# Simple-BUG-BC557.net
KiCad netlist of a schematic drawn in EAGLE
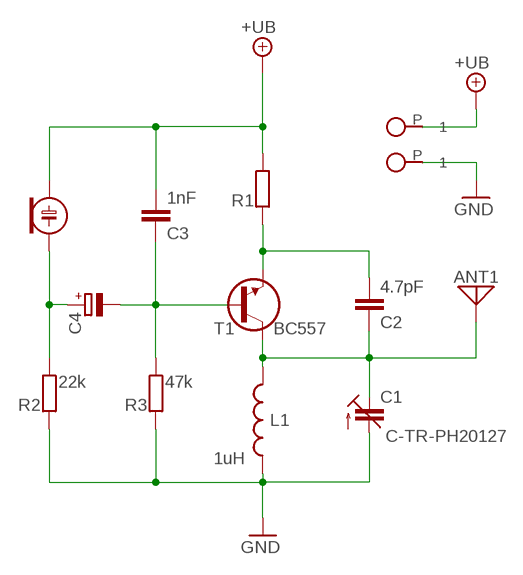
[diagram p0: schematic, sheet 1]

(export (version "E")
  (design (tool "Eeschema 10.0.6"))
  (components
    (comp (ref "+")
      (value "SPAD")
      (footprint "eagle-import:SPAD")
      (libsource (lib "eagle-import") (part "SPAD"))
    )
    (comp (ref "ANT1")
      (value "ANT")
      (footprint "eagle-import:SPAD")
      (libsource (lib "eagle-import") (part "ANT"))
    )
    (comp (ref "C1")
      (value "C-TR-PH20127")
      (footprint "eagle-import:TRIM808-45")
      (libsource (lib "eagle-import") (part "C-TR-PH20127-45-2P23"))
    )
    (comp (ref "C2")
      (value "4.7pF")
      (footprint "eagle-import:C050-020X036")
      (libsource (lib "eagle-import") (part "C050-020X036"))
    )
    (comp (ref "C3")
      (value "1nF")
      (footprint "eagle-import:C050-020X036")
      (libsource (lib "eagle-import") (part "C050-020X036"))
    )
    (comp (ref "C4")
      (value "CPOLE2,5-3")
      (footprint "eagle-import:E2,5-3")
      (libsource (lib "eagle-import") (part "CPOLE2,5-3"))
    )
    (comp (ref "ECM")
      (value "ECM-5")
      (footprint "eagle-import:ECM-5")
      (libsource (lib "eagle-import") (part "ECM-5"))
    )
    (comp (ref "L1")
      (value "1uH")
      (footprint "eagle-import:L-04_7")
      (libsource (lib "eagle-import") (part "L04/7"))
    )
    (comp (ref "R1")
      (value "R0202V")
      (footprint "eagle-import:0202V")
      (libsource (lib "eagle-import") (part "R0202V"))
    )
    (comp (ref "R2")
      (value "22k")
      (footprint "eagle-import:0202_5")
      (libsource (lib "eagle-import") (part "R0202/5"))
    )
    (comp (ref "R3")
      (value "47k")
      (footprint "eagle-import:0202_5")
      (libsource (lib "eagle-import") (part "R0202/5"))
    )
    (comp (ref "T1")
      (value "BC557")
      (footprint "eagle-import:TO92-CBE-A")
      (libsource (lib "eagle-import") (part "BC547CBE-A"))
    )
    (comp (ref "̶̶")
      (value "SPAD")
      (footprint "eagle-import:SPAD")
      (libsource (lib "eagle-import") (part "SPAD"))
    )
  )
  (nets
    (net (code "1") (name "+UB") (class "Default")
      (node (ref "+") (pin "P") (pinfunction "1_P") (pintype "bidirectional"))
      (node (ref "C3") (pin "2") (pinfunction "2_2") (pintype "passive"))
      (node (ref "ECM") (pin "1") (pinfunction "+_1") (pintype "passive"))
      (node (ref "R1") (pin "1") (pinfunction "1_1") (pintype "passive"))
    )
    (net (code "2") (name "GND") (class "Default")
      (node (ref "C1") (pin "2") (pinfunction "A_2") (pintype "passive"))
      (node (ref "L1") (pin "2") (pinfunction "2_2") (pintype "passive"))
      (node (ref "R2") (pin "2") (pinfunction "2_2") (pintype "passive"))
      (node (ref "R3") (pin "2") (pinfunction "2_2") (pintype "passive"))
      (node (ref "̶̶") (pin "P") (pinfunction "1_P") (pintype "bidirectional"))
    )
    (net (code "3") (name "Net-(ANT1-1)") (class "Default")
      (node (ref "ANT1") (pin "P") (pinfunction "1_P") (pintype "output"))
      (node (ref "C1") (pin "3") (pinfunction "E_3") (pintype "passive"))
      (node (ref "C2") (pin "1") (pinfunction "1_1") (pintype "passive"))
      (node (ref "L1") (pin "1") (pinfunction "1_1") (pintype "passive"))
      (node (ref "T1") (pin "C") (pinfunction "C_C") (pintype "passive"))
    )
    (net (code "4") (name "Net-(C2-Pad2)") (class "Default")
      (node (ref "C2") (pin "2") (pinfunction "2_2") (pintype "passive"))
      (node (ref "R1") (pin "2") (pinfunction "2_2") (pintype "passive"))
      (node (ref "T1") (pin "E") (pinfunction "E_E") (pintype "passive"))
    )
    (net (code "5") (name "Net-(C3-Pad1)") (class "Default")
      (node (ref "C3") (pin "1") (pinfunction "1_1") (pintype "passive"))
      (node (ref "C4") (pin "-") (pinfunction "-_-") (pintype "passive"))
      (node (ref "R3") (pin "1") (pinfunction "1_1") (pintype "passive"))
      (node (ref "T1") (pin "B") (pinfunction "B_B") (pintype "passive"))
    )
    (net (code "6") (name "Net-(ECM--)") (class "Default")
      (node (ref "C4") (pin "+") (pinfunction "+_+") (pintype "passive"))
      (node (ref "ECM") (pin "2") (pinfunction "-_2") (pintype "passive"))
      (node (ref "R2") (pin "1") (pinfunction "1_1") (pintype "passive"))
    )
  )
)
